# Schematic_V0_1.net
KiCad netlist of a schematic drawn in EAGLE
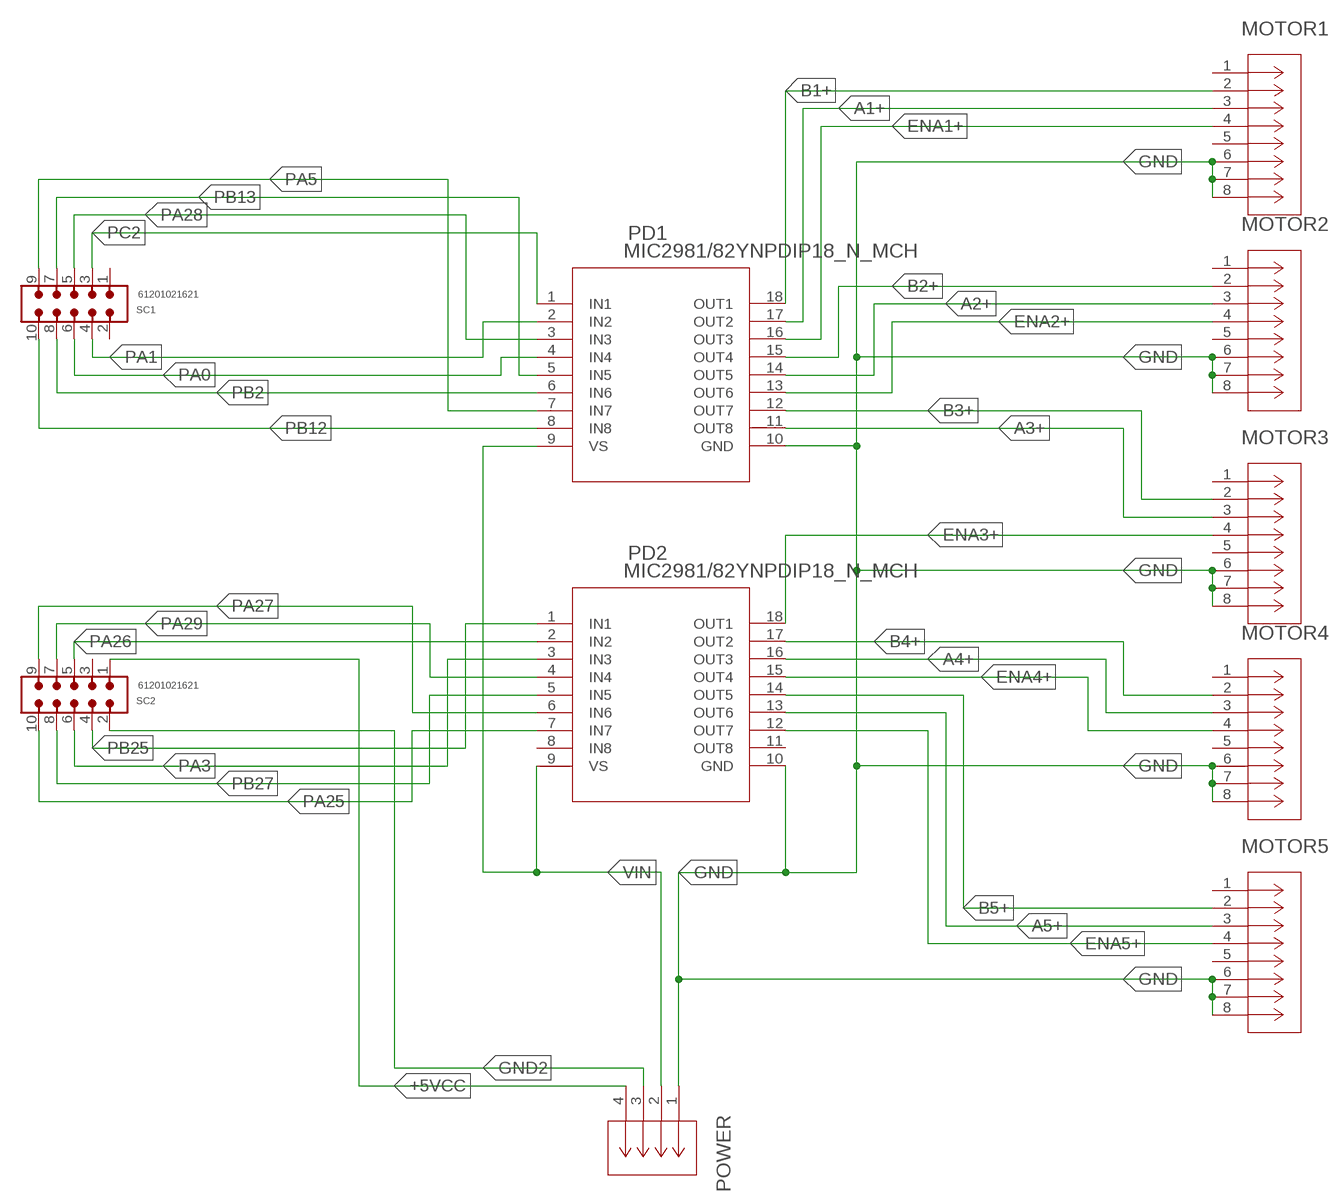
[diagram p0: schematic, sheet 1]

(export (version "E")
  (design (tool "Eeschema 10.0.6"))
  (components
    (comp (ref "MOTOR1")
      (value "1724470208CON_1724470208")
      (footprint "eagle-import:CON_1724470208")
      (fields
        (field (name "MANUFACTURER_PART_NUMBER") "1724470208")
        (field (name "COPYRIGHT") "Copyright (C) 2024 Ultra Librarian. All rights reserved.")
      )
      (libsource (lib "eagle-import") (part "1724470208CON_1724470208"))
    )
    (comp (ref "MOTOR2")
      (value "1724470208CON_1724470208")
      (footprint "eagle-import:CON_1724470208")
      (fields
        (field (name "MANUFACTURER_PART_NUMBER") "1724470208")
        (field (name "COPYRIGHT") "Copyright (C) 2024 Ultra Librarian. All rights reserved.")
      )
      (libsource (lib "eagle-import") (part "1724470208CON_1724470208"))
    )
    (comp (ref "MOTOR3")
      (value "1724470208CON_1724470208")
      (footprint "eagle-import:CON_1724470208")
      (fields
        (field (name "MANUFACTURER_PART_NUMBER") "1724470208")
        (field (name "COPYRIGHT") "Copyright (C) 2024 Ultra Librarian. All rights reserved.")
      )
      (libsource (lib "eagle-import") (part "1724470208CON_1724470208"))
    )
    (comp (ref "MOTOR4")
      (value "1724470208CON_1724470208")
      (footprint "eagle-import:CON_1724470208")
      (fields
        (field (name "MANUFACTURER_PART_NUMBER") "1724470208")
        (field (name "COPYRIGHT") "Copyright (C) 2024 Ultra Librarian. All rights reserved.")
      )
      (libsource (lib "eagle-import") (part "1724470208CON_1724470208"))
    )
    (comp (ref "MOTOR5")
      (value "1724470208CON_1724470208")
      (footprint "eagle-import:CON_1724470208")
      (fields
        (field (name "MANUFACTURER_PART_NUMBER") "1724470208")
        (field (name "COPYRIGHT") "Copyright (C) 2024 Ultra Librarian. All rights reserved.")
      )
      (libsource (lib "eagle-import") (part "1724470208CON_1724470208"))
    )
    (comp (ref "PD1")
      (value "MIC2981/82YNPDIP18_N_MCH")
      (footprint "eagle-import:PDIP18_N_MCH")
      (fields
        (field (name "MANUFACTURER_PART_NUMBER") "MIC2981/82YN")
        (field (name "COPYRIGHT") "Copyright (C) 2024 Ultra Librarian. All rights reserved.")
      )
      (libsource (lib "eagle-import") (part "MIC2981/82YNPDIP18_N_MCH"))
    )
    (comp (ref "PD2")
      (value "MIC2981/82YNPDIP18_N_MCH")
      (footprint "eagle-import:PDIP18_N_MCH")
      (fields
        (field (name "MANUFACTURER_PART_NUMBER") "MIC2981/82YN")
        (field (name "COPYRIGHT") "Copyright (C) 2024 Ultra Librarian. All rights reserved.")
      )
      (libsource (lib "eagle-import") (part "MIC2981/82YNPDIP18_N_MCH"))
    )
    (comp (ref "POWER")
      (value "OSTYK42104030CONN4_K42104030_OST")
      (footprint "eagle-import:CONN4_K42104030_OST")
      (fields
        (field (name "MANUFACTURER_PART_NUMBER") "OSTYK42104030")
        (field (name "COPYRIGHT") "Copyright (C) 2024 Ultra Librarian. All rights reserved.")
      )
      (libsource (lib "eagle-import") (part "OSTYK42104030CONN4_K42104030_OST"))
    )
    (comp (ref "SC1")
      (value "61201021621")
      (footprint "eagle-import:61201021621")
      (libsource (lib "eagle-import") (part "6120XX21621_61201021621"))
    )
    (comp (ref "SC2")
      (value "61201021621")
      (footprint "eagle-import:61201021621")
      (libsource (lib "eagle-import") (part "6120XX21621_61201021621"))
    )
  )
  (nets
    (net (code "1") (name "+5VCC") (class "Default")
      (node (ref "POWER") (pin "4") (pinfunction "4_4") (pintype "passive"))
      (node (ref "SC2") (pin "1") (pinfunction "1_1") (pintype "passive"))
    )
    (net (code "2") (name "A1+") (class "Default")
      (node (ref "MOTOR1") (pin "3") (pinfunction "3_3") (pintype "passive"))
      (node (ref "PD1") (pin "17") (pinfunction "OUT2_17") (pintype "output"))
    )
    (net (code "3") (name "A2+") (class "Default")
      (node (ref "MOTOR2") (pin "3") (pinfunction "3_3") (pintype "passive"))
      (node (ref "PD1") (pin "14") (pinfunction "OUT5_14") (pintype "output"))
    )
    (net (code "4") (name "A3+") (class "Default")
      (node (ref "MOTOR3") (pin "3") (pinfunction "3_3") (pintype "passive"))
      (node (ref "PD1") (pin "11") (pinfunction "OUT8_11") (pintype "output"))
    )
    (net (code "5") (name "A4+") (class "Default")
      (node (ref "MOTOR4") (pin "3") (pinfunction "3_3") (pintype "passive"))
      (node (ref "PD2") (pin "16") (pinfunction "OUT3_16") (pintype "output"))
    )
    (net (code "6") (name "A5+") (class "Default")
      (node (ref "MOTOR5") (pin "3") (pinfunction "3_3") (pintype "passive"))
      (node (ref "PD2") (pin "13") (pinfunction "OUT6_13") (pintype "output"))
    )
    (net (code "7") (name "B1+") (class "Default")
      (node (ref "MOTOR1") (pin "2") (pinfunction "2_2") (pintype "passive"))
      (node (ref "PD1") (pin "18") (pinfunction "OUT1_18") (pintype "output"))
    )
    (net (code "8") (name "B2+") (class "Default")
      (node (ref "MOTOR2") (pin "2") (pinfunction "2_2") (pintype "passive"))
      (node (ref "PD1") (pin "15") (pinfunction "OUT4_15") (pintype "output"))
    )
    (net (code "9") (name "B3+") (class "Default")
      (node (ref "MOTOR3") (pin "2") (pinfunction "2_2") (pintype "passive"))
      (node (ref "PD1") (pin "12") (pinfunction "OUT7_12") (pintype "output"))
    )
    (net (code "10") (name "B4+") (class "Default")
      (node (ref "MOTOR4") (pin "2") (pinfunction "2_2") (pintype "passive"))
      (node (ref "PD2") (pin "17") (pinfunction "OUT2_17") (pintype "output"))
    )
    (net (code "11") (name "B5+") (class "Default")
      (node (ref "MOTOR5") (pin "2") (pinfunction "2_2") (pintype "passive"))
      (node (ref "PD2") (pin "14") (pinfunction "OUT5_14") (pintype "output"))
    )
    (net (code "12") (name "ENA1+") (class "Default")
      (node (ref "MOTOR1") (pin "4") (pinfunction "4_4") (pintype "passive"))
      (node (ref "PD1") (pin "16") (pinfunction "OUT3_16") (pintype "output"))
    )
    (net (code "13") (name "ENA2+") (class "Default")
      (node (ref "MOTOR2") (pin "4") (pinfunction "4_4") (pintype "passive"))
      (node (ref "PD1") (pin "13") (pinfunction "OUT6_13") (pintype "output"))
    )
    (net (code "14") (name "ENA3+") (class "Default")
      (node (ref "MOTOR3") (pin "4") (pinfunction "4_4") (pintype "passive"))
      (node (ref "PD2") (pin "18") (pinfunction "OUT1_18") (pintype "output"))
    )
    (net (code "15") (name "ENA4+") (class "Default")
      (node (ref "MOTOR4") (pin "4") (pinfunction "4_4") (pintype "passive"))
      (node (ref "PD2") (pin "15") (pinfunction "OUT4_15") (pintype "output"))
    )
    (net (code "16") (name "ENA5+") (class "Default")
      (node (ref "MOTOR5") (pin "4") (pinfunction "4_4") (pintype "passive"))
      (node (ref "PD2") (pin "12") (pinfunction "OUT7_12") (pintype "output"))
    )
    (net (code "17") (name "GND") (class "Default")
      (node (ref "MOTOR1") (pin "6") (pinfunction "6_6") (pintype "passive"))
      (node (ref "MOTOR1") (pin "7") (pinfunction "7_7") (pintype "passive"))
      (node (ref "MOTOR1") (pin "8") (pinfunction "8_8") (pintype "passive"))
      (node (ref "MOTOR2") (pin "6") (pinfunction "6_6") (pintype "passive"))
      (node (ref "MOTOR2") (pin "7") (pinfunction "7_7") (pintype "passive"))
      (node (ref "MOTOR2") (pin "8") (pinfunction "8_8") (pintype "passive"))
      (node (ref "MOTOR3") (pin "6") (pinfunction "6_6") (pintype "passive"))
      (node (ref "MOTOR3") (pin "7") (pinfunction "7_7") (pintype "passive"))
      (node (ref "MOTOR3") (pin "8") (pinfunction "8_8") (pintype "passive"))
      (node (ref "MOTOR4") (pin "6") (pinfunction "6_6") (pintype "passive"))
      (node (ref "MOTOR4") (pin "7") (pinfunction "7_7") (pintype "passive"))
      (node (ref "MOTOR4") (pin "8") (pinfunction "8_8") (pintype "passive"))
      (node (ref "MOTOR5") (pin "6") (pinfunction "6_6") (pintype "passive"))
      (node (ref "MOTOR5") (pin "7") (pinfunction "7_7") (pintype "passive"))
      (node (ref "MOTOR5") (pin "8") (pinfunction "8_8") (pintype "passive"))
      (node (ref "PD1") (pin "10") (pinfunction "GND_10") (pintype "passive"))
      (node (ref "PD2") (pin "10") (pinfunction "GND_10") (pintype "passive"))
      (node (ref "POWER") (pin "1") (pinfunction "1_1") (pintype "passive"))
    )
    (net (code "18") (name "GND2") (class "Default")
      (node (ref "POWER") (pin "3") (pinfunction "3_3") (pintype "passive"))
      (node (ref "SC2") (pin "2") (pinfunction "2_2") (pintype "passive"))
    )
    (net (code "19") (name "PA0") (class "Default")
      (node (ref "PD1") (pin "4") (pinfunction "IN4_4") (pintype "input"))
      (node (ref "SC1") (pin "6") (pinfunction "6_6") (pintype "passive"))
    )
    (net (code "20") (name "PA1") (class "Default")
      (node (ref "PD1") (pin "2") (pinfunction "IN2_2") (pintype "input"))
      (node (ref "SC1") (pin "4") (pinfunction "4_4") (pintype "passive"))
    )
    (net (code "21") (name "PA3") (class "Default")
      (node (ref "PD2") (pin "3") (pinfunction "IN3_3") (pintype "input"))
      (node (ref "SC2") (pin "6") (pinfunction "6_6") (pintype "passive"))
    )
    (net (code "22") (name "PA5") (class "Default")
      (node (ref "PD1") (pin "7") (pinfunction "IN7_7") (pintype "input"))
      (node (ref "SC1") (pin "9") (pinfunction "9_9") (pintype "passive"))
    )
    (net (code "23") (name "PA25") (class "Default")
      (node (ref "PD2") (pin "7") (pinfunction "IN7_7") (pintype "input"))
      (node (ref "SC2") (pin "10") (pinfunction "10_10") (pintype "passive"))
    )
    (net (code "24") (name "PA26") (class "Default")
      (node (ref "PD2") (pin "2") (pinfunction "IN2_2") (pintype "input"))
      (node (ref "SC2") (pin "5") (pinfunction "5_5") (pintype "passive"))
    )
    (net (code "25") (name "PA27") (class "Default")
      (node (ref "PD2") (pin "6") (pinfunction "IN6_6") (pintype "input"))
      (node (ref "SC2") (pin "9") (pinfunction "9_9") (pintype "passive"))
    )
    (net (code "26") (name "PA28") (class "Default")
      (node (ref "PD1") (pin "3") (pinfunction "IN3_3") (pintype "input"))
      (node (ref "SC1") (pin "5") (pinfunction "5_5") (pintype "passive"))
    )
    (net (code "27") (name "PA29") (class "Default")
      (node (ref "PD2") (pin "4") (pinfunction "IN4_4") (pintype "input"))
      (node (ref "SC2") (pin "7") (pinfunction "7_7") (pintype "passive"))
    )
    (net (code "28") (name "PB2") (class "Default")
      (node (ref "PD1") (pin "6") (pinfunction "IN6_6") (pintype "input"))
      (node (ref "SC1") (pin "8") (pinfunction "8_8") (pintype "passive"))
    )
    (net (code "29") (name "PB12") (class "Default")
      (node (ref "PD1") (pin "8") (pinfunction "IN8_8") (pintype "input"))
      (node (ref "SC1") (pin "10") (pinfunction "10_10") (pintype "passive"))
    )
    (net (code "30") (name "PB13") (class "Default")
      (node (ref "PD1") (pin "5") (pinfunction "IN5_5") (pintype "input"))
      (node (ref "SC1") (pin "7") (pinfunction "7_7") (pintype "passive"))
    )
    (net (code "31") (name "PB25") (class "Default")
      (node (ref "PD2") (pin "1") (pinfunction "IN1_1") (pintype "input"))
      (node (ref "SC2") (pin "4") (pinfunction "4_4") (pintype "passive"))
    )
    (net (code "32") (name "PB27") (class "Default")
      (node (ref "PD2") (pin "5") (pinfunction "IN5_5") (pintype "input"))
      (node (ref "SC2") (pin "8") (pinfunction "8_8") (pintype "passive"))
    )
    (net (code "33") (name "PC2") (class "Default")
      (node (ref "PD1") (pin "1") (pinfunction "IN1_1") (pintype "input"))
      (node (ref "SC1") (pin "3") (pinfunction "3_3") (pintype "passive"))
    )
    (net (code "34") (name "VIN") (class "Default")
      (node (ref "PD1") (pin "9") (pinfunction "VS_9") (pintype "power_in"))
      (node (ref "PD2") (pin "9") (pinfunction "VS_9") (pintype "power_in"))
      (node (ref "POWER") (pin "2") (pinfunction "2_2") (pintype "passive"))
    )
    (net (code "35") (name "unconnected-(MOTOR1-Pad1)") (class "Default")
      (node (ref "MOTOR1") (pin "1") (pinfunction "1_1") (pintype "passive"))
    )
    (net (code "36") (name "unconnected-(MOTOR1-Pad5)") (class "Default")
      (node (ref "MOTOR1") (pin "5") (pinfunction "5_5") (pintype "passive"))
    )
    (net (code "37") (name "unconnected-(MOTOR2-Pad1)") (class "Default")
      (node (ref "MOTOR2") (pin "1") (pinfunction "1_1") (pintype "passive"))
    )
    (net (code "38") (name "unconnected-(MOTOR2-Pad5)") (class "Default")
      (node (ref "MOTOR2") (pin "5") (pinfunction "5_5") (pintype "passive"))
    )
    (net (code "39") (name "unconnected-(MOTOR3-Pad1)") (class "Default")
      (node (ref "MOTOR3") (pin "1") (pinfunction "1_1") (pintype "passive"))
    )
    (net (code "40") (name "unconnected-(MOTOR3-Pad5)") (class "Default")
      (node (ref "MOTOR3") (pin "5") (pinfunction "5_5") (pintype "passive"))
    )
    (net (code "41") (name "unconnected-(MOTOR4-Pad1)") (class "Default")
      (node (ref "MOTOR4") (pin "1") (pinfunction "1_1") (pintype "passive"))
    )
    (net (code "42") (name "unconnected-(MOTOR4-Pad5)") (class "Default")
      (node (ref "MOTOR4") (pin "5") (pinfunction "5_5") (pintype "passive"))
    )
    (net (code "43") (name "unconnected-(MOTOR5-Pad1)") (class "Default")
      (node (ref "MOTOR5") (pin "1") (pinfunction "1_1") (pintype "passive"))
    )
    (net (code "44") (name "unconnected-(MOTOR5-Pad5)") (class "Default")
      (node (ref "MOTOR5") (pin "5") (pinfunction "5_5") (pintype "passive"))
    )
    (net (code "45") (name "unconnected-(PD2-IN8-Pad8)") (class "Default")
      (node (ref "PD2") (pin "8") (pinfunction "IN8_8") (pintype "input"))
    )
    (net (code "46") (name "unconnected-(PD2-OUT8-Pad11)") (class "Default")
      (node (ref "PD2") (pin "11") (pinfunction "OUT8_11") (pintype "output"))
    )
    (net (code "47") (name "unconnected-(SC1-Pad1)") (class "Default")
      (node (ref "SC1") (pin "1") (pinfunction "1_1") (pintype "passive"))
    )
    (net (code "48") (name "unconnected-(SC1-Pad2)") (class "Default")
      (node (ref "SC1") (pin "2") (pinfunction "2_2") (pintype "passive"))
    )
    (net (code "49") (name "unconnected-(SC2-Pad3)") (class "Default")
      (node (ref "SC2") (pin "3") (pinfunction "3_3") (pintype "passive"))
    )
  )
)
